# BIO26_sensor_connect.net
KiCad netlist of a schematic drawn in Altium Designer
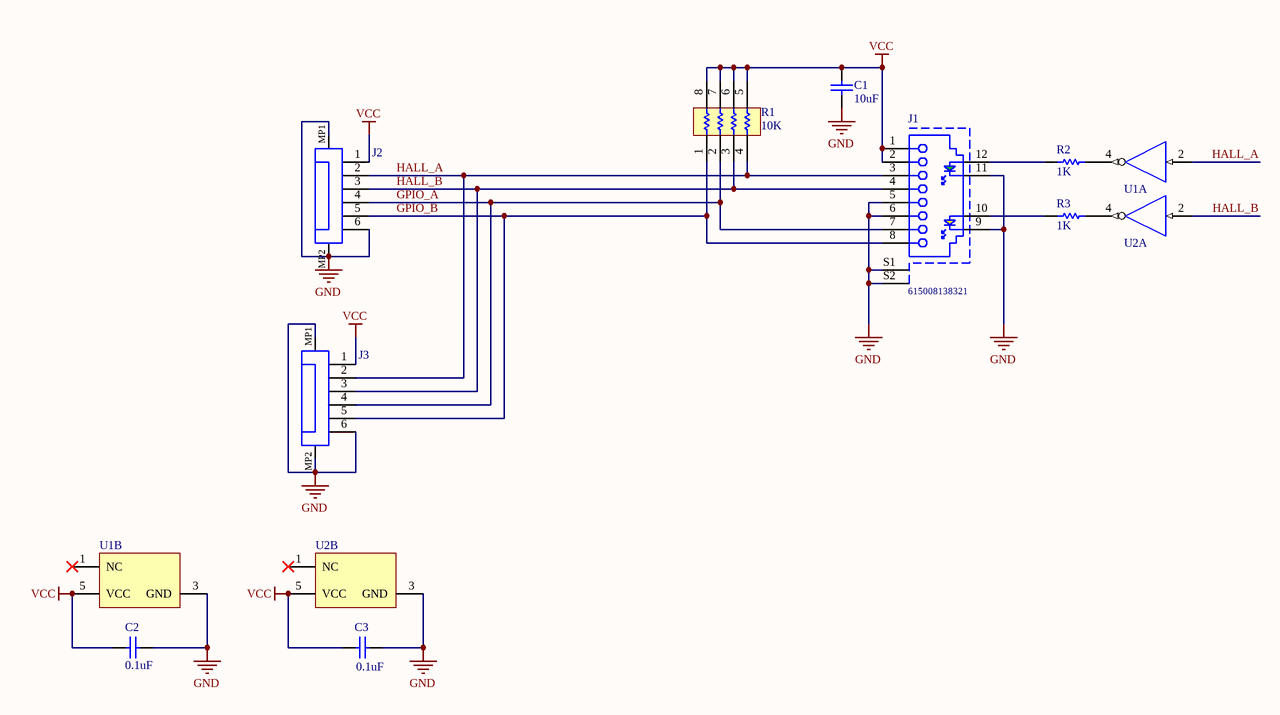
[diagram p0: BIO26_sensor_connect.SchDoc]

(export (version "E")
  (design (tool "Eeschema 10.0.6"))
  (components
    (comp (ref "C1")
      (value "10uF")
      (footprint "CAPC2013X140X50LL20T25")
      (fields (field (name "PART NUMBER") "C0805C106K8PACTU") (field (name "MANUFACTURER") "Kemet"))
      (libsource (lib "Altium Content Vault") (part "CAP"))
    )
    (comp (ref "C2")
      (value "0.1uF")
      (footprint "CAPC1608X87X35NL15T15")
      (fields (field (name "PART NUMBER") "C0603X104K5RACTU") (field (name "MANUFACTURER") "Kemet"))
      (libsource (lib "Altium Content Vault") (part "CAP"))
    )
    (comp (ref "C3")
      (value "0.1uF")
      (footprint "CAPC1608X87X35NL15T15")
      (fields (field (name "PART NUMBER") "C0603X104K5RACTU") (field (name "MANUFACTURER") "Kemet"))
      (libsource (lib "Altium Content Vault") (part "CAP"))
    )
    (comp (ref "J1")
      (value "615008138321")
      (footprint "615008138321")
      (description "Modular Jack WR-MJ, Shielded, with LED, Vertical Entry, THT, 8P8C")
      (fields (field (name "MANUFACTURER") "Wurth Elektronik") (field (name "PUBLISHER") "WurthElektronik"))
      (libsource (lib "Altium Content Vault") (part "WE-RJ45-12-2SHLD_A"))
    )
    (comp (ref "J2")
      (value "68610614422")
      (footprint "68610614422")
      (description "SMT ZIF Connectors WR-FPC, Horizontal, Bottom Contact, pitch 1 mm, 6 pins")
      (fields (field (name "MANUFACTURER") "Wurth Elektronik") (field (name "PUBLISHER") "WurthElektronik"))
      (libsource (lib "Altium Content Vault") (part "WE-68X1061XXX22-6"))
    )
    (comp (ref "J3")
      (value "68610614422")
      (footprint "68610614422")
      (description "SMT ZIF Connectors WR-FPC, Horizontal, Bottom Contact, pitch 1 mm, 6 pins")
      (fields (field (name "MANUFACTURER") "Wurth Elektronik") (field (name "PUBLISHER") "WurthElektronik"))
      (libsource (lib "Altium Content Vault") (part "WE-68X1061XXX22-6"))
    )
    (comp (ref "R1")
      (value "10K")
      (footprint "BOUR-CAY16-J4_V")
      (description "Chip Resistor Array, 10 KOhm, +/- 5%, 62.5 mW, -55 to 125 degC, 8-Pin SMD, RoHS, Tape and Reel")
      (fields (field (name "TOLERANCE") "1%"))
      (libsource (lib "Altium Content Vault") (part "RES-P-8"))
    )
    (comp (ref "R2")
      (value "1K")
      (footprint "RESC1608X55X30ML15T15")
      (fields (field (name "PART NUMBER") "ERJ-3GEYJ102V") (field (name "MANUFACTURER") "Panasonic"))
      (libsource (lib "Altium Content Vault") (part "RES"))
    )
    (comp (ref "R3")
      (value "1K")
      (footprint "RESC1608X55X30ML15T15")
      (fields (field (name "PART NUMBER") "ERJ-3GEYJ102V") (field (name "MANUFACTURER") "Panasonic"))
      (libsource (lib "Altium Content Vault") (part "RES"))
    )
    (comp (ref "U1")
      (value "SN74AHC1G14DBVR")
      (footprint "DBV0005A_L")
      (fields (field (name "MANUFACTURER") "Texas Instruments"))
      (libsource (lib "Altium Content Vault") (part "TI-SN74XXX1XX4-XX-5"))
    )
    (comp (ref "U2")
      (value "SN74AHC1G14DBVR")
      (footprint "DBV0005A_L")
      (fields (field (name "MANUFACTURER") "Texas Instruments"))
      (libsource (lib "Altium Content Vault") (part "TI-SN74XXX1XX4-XX-5"))
    )
  )
  (nets
    (net (code "1") (name "/GPIO_A") (class "Default")
      (node (ref "J1") (pin "7") (pinfunction "7_7") (pintype "passive"))
      (node (ref "J2") (pin "4") (pinfunction "4_4") (pintype "passive"))
      (node (ref "J3") (pin "4") (pinfunction "4_4") (pintype "passive"))
      (node (ref "R1") (pin "2") (pinfunction "2_2") (pintype "passive"))
    )
    (net (code "2") (name "/GPIO_B") (class "Default")
      (node (ref "J1") (pin "8") (pinfunction "8_8") (pintype "passive"))
      (node (ref "J2") (pin "5") (pinfunction "5_5") (pintype "passive"))
      (node (ref "J3") (pin "5") (pinfunction "5_5") (pintype "passive"))
      (node (ref "R1") (pin "1") (pinfunction "1_1") (pintype "passive"))
    )
    (net (code "3") (name "/HALL_A") (class "Default")
      (node (ref "J1") (pin "3") (pinfunction "3_3") (pintype "passive"))
      (node (ref "J2") (pin "2") (pinfunction "2_2") (pintype "passive"))
      (node (ref "J3") (pin "2") (pinfunction "2_2") (pintype "passive"))
      (node (ref "R1") (pin "4") (pinfunction "4_4") (pintype "passive"))
      (node (ref "U1") (pin "2") (pinfunction "A_2") (pintype "input"))
    )
    (net (code "4") (name "/HALL_B") (class "Default")
      (node (ref "J1") (pin "4") (pinfunction "4_4") (pintype "passive"))
      (node (ref "J2") (pin "3") (pinfunction "3_3") (pintype "passive"))
      (node (ref "J3") (pin "3") (pinfunction "3_3") (pintype "passive"))
      (node (ref "R1") (pin "3") (pinfunction "3_3") (pintype "passive"))
      (node (ref "U2") (pin "2") (pinfunction "A_2") (pintype "input"))
    )
    (net (code "5") (name "GND") (class "Default")
      (node (ref "C1") (pin "1") (pinfunction "1_1") (pintype "passive"))
      (node (ref "C2") (pin "2") (pinfunction "2_2") (pintype "passive"))
      (node (ref "C3") (pin "2") (pinfunction "2_2") (pintype "passive"))
      (node (ref "J1") (pin "11") (pinfunction "11_11") (pintype "passive"))
      (node (ref "J1") (pin "5") (pinfunction "5_5") (pintype "passive"))
      (node (ref "J1") (pin "6") (pinfunction "6_6") (pintype "passive"))
      (node (ref "J1") (pin "9") (pinfunction "9_9") (pintype "passive"))
      (node (ref "J1") (pin "S1") (pinfunction "S1_S1") (pintype "passive"))
      (node (ref "J1") (pin "S2") (pinfunction "S2_S2") (pintype "passive"))
      (node (ref "J2") (pin "6") (pinfunction "6_6") (pintype "passive"))
      (node (ref "J2") (pin "MP1") (pinfunction "MP1_MP1") (pintype "passive"))
      (node (ref "J2") (pin "MP2") (pinfunction "MP2_MP2") (pintype "passive"))
      (node (ref "J3") (pin "6") (pinfunction "6_6") (pintype "passive"))
      (node (ref "J3") (pin "MP1") (pinfunction "MP1_MP1") (pintype "passive"))
      (node (ref "J3") (pin "MP2") (pinfunction "MP2_MP2") (pintype "passive"))
      (node (ref "U1") (pin "3") (pinfunction "GND_3") (pintype "power_in"))
      (node (ref "U2") (pin "3") (pinfunction "GND_3") (pintype "power_in"))
    )
    (net (code "6") (name "Net-(J1-Pad10)") (class "Default")
      (node (ref "J1") (pin "10") (pinfunction "10_10") (pintype "passive"))
      (node (ref "R3") (pin "2") (pinfunction "2_2") (pintype "passive"))
    )
    (net (code "7") (name "Net-(J1-Pad12)") (class "Default")
      (node (ref "J1") (pin "12") (pinfunction "12_12") (pintype "passive"))
      (node (ref "R2") (pin "2") (pinfunction "2_2") (pintype "passive"))
    )
    (net (code "8") (name "Net-(U1A-Y)") (class "Default")
      (node (ref "R2") (pin "1") (pinfunction "1_1") (pintype "passive"))
      (node (ref "U1") (pin "4") (pinfunction "Y_4") (pintype "output"))
    )
    (net (code "9") (name "Net-(U2A-Y)") (class "Default")
      (node (ref "R3") (pin "1") (pinfunction "1_1") (pintype "passive"))
      (node (ref "U2") (pin "4") (pinfunction "Y_4") (pintype "output"))
    )
    (net (code "10") (name "VCC") (class "Default")
      (node (ref "C1") (pin "2") (pinfunction "2_2") (pintype "passive"))
      (node (ref "C2") (pin "1") (pinfunction "1_1") (pintype "passive"))
      (node (ref "C3") (pin "1") (pinfunction "1_1") (pintype "passive"))
      (node (ref "J1") (pin "1") (pinfunction "1_1") (pintype "passive"))
      (node (ref "J1") (pin "2") (pinfunction "2_2") (pintype "passive"))
      (node (ref "J2") (pin "1") (pinfunction "1_1") (pintype "passive"))
      (node (ref "J3") (pin "1") (pinfunction "1_1") (pintype "passive"))
      (node (ref "R1") (pin "5") (pinfunction "5_5") (pintype "passive"))
      (node (ref "R1") (pin "6") (pinfunction "6_6") (pintype "passive"))
      (node (ref "R1") (pin "7") (pinfunction "7_7") (pintype "passive"))
      (node (ref "R1") (pin "8") (pinfunction "8_8") (pintype "passive"))
      (node (ref "U1") (pin "5") (pinfunction "VCC_5") (pintype "power_in"))
      (node (ref "U2") (pin "5") (pinfunction "VCC_5") (pintype "power_in"))
    )
    (net (code "11") (name "unconnected-(U1B-NC-Pad1)") (class "Default")
      (node (ref "U1") (pin "1") (pinfunction "NC_1") (pintype "passive+no_connect"))
    )
    (net (code "12") (name "unconnected-(U2B-NC-Pad1)") (class "Default")
      (node (ref "U2") (pin "1") (pinfunction "NC_1") (pintype "passive+no_connect"))
    )
  )
)
